# connector_schematic_1.net
KiCad netlist of a schematic drawn in EAGLE
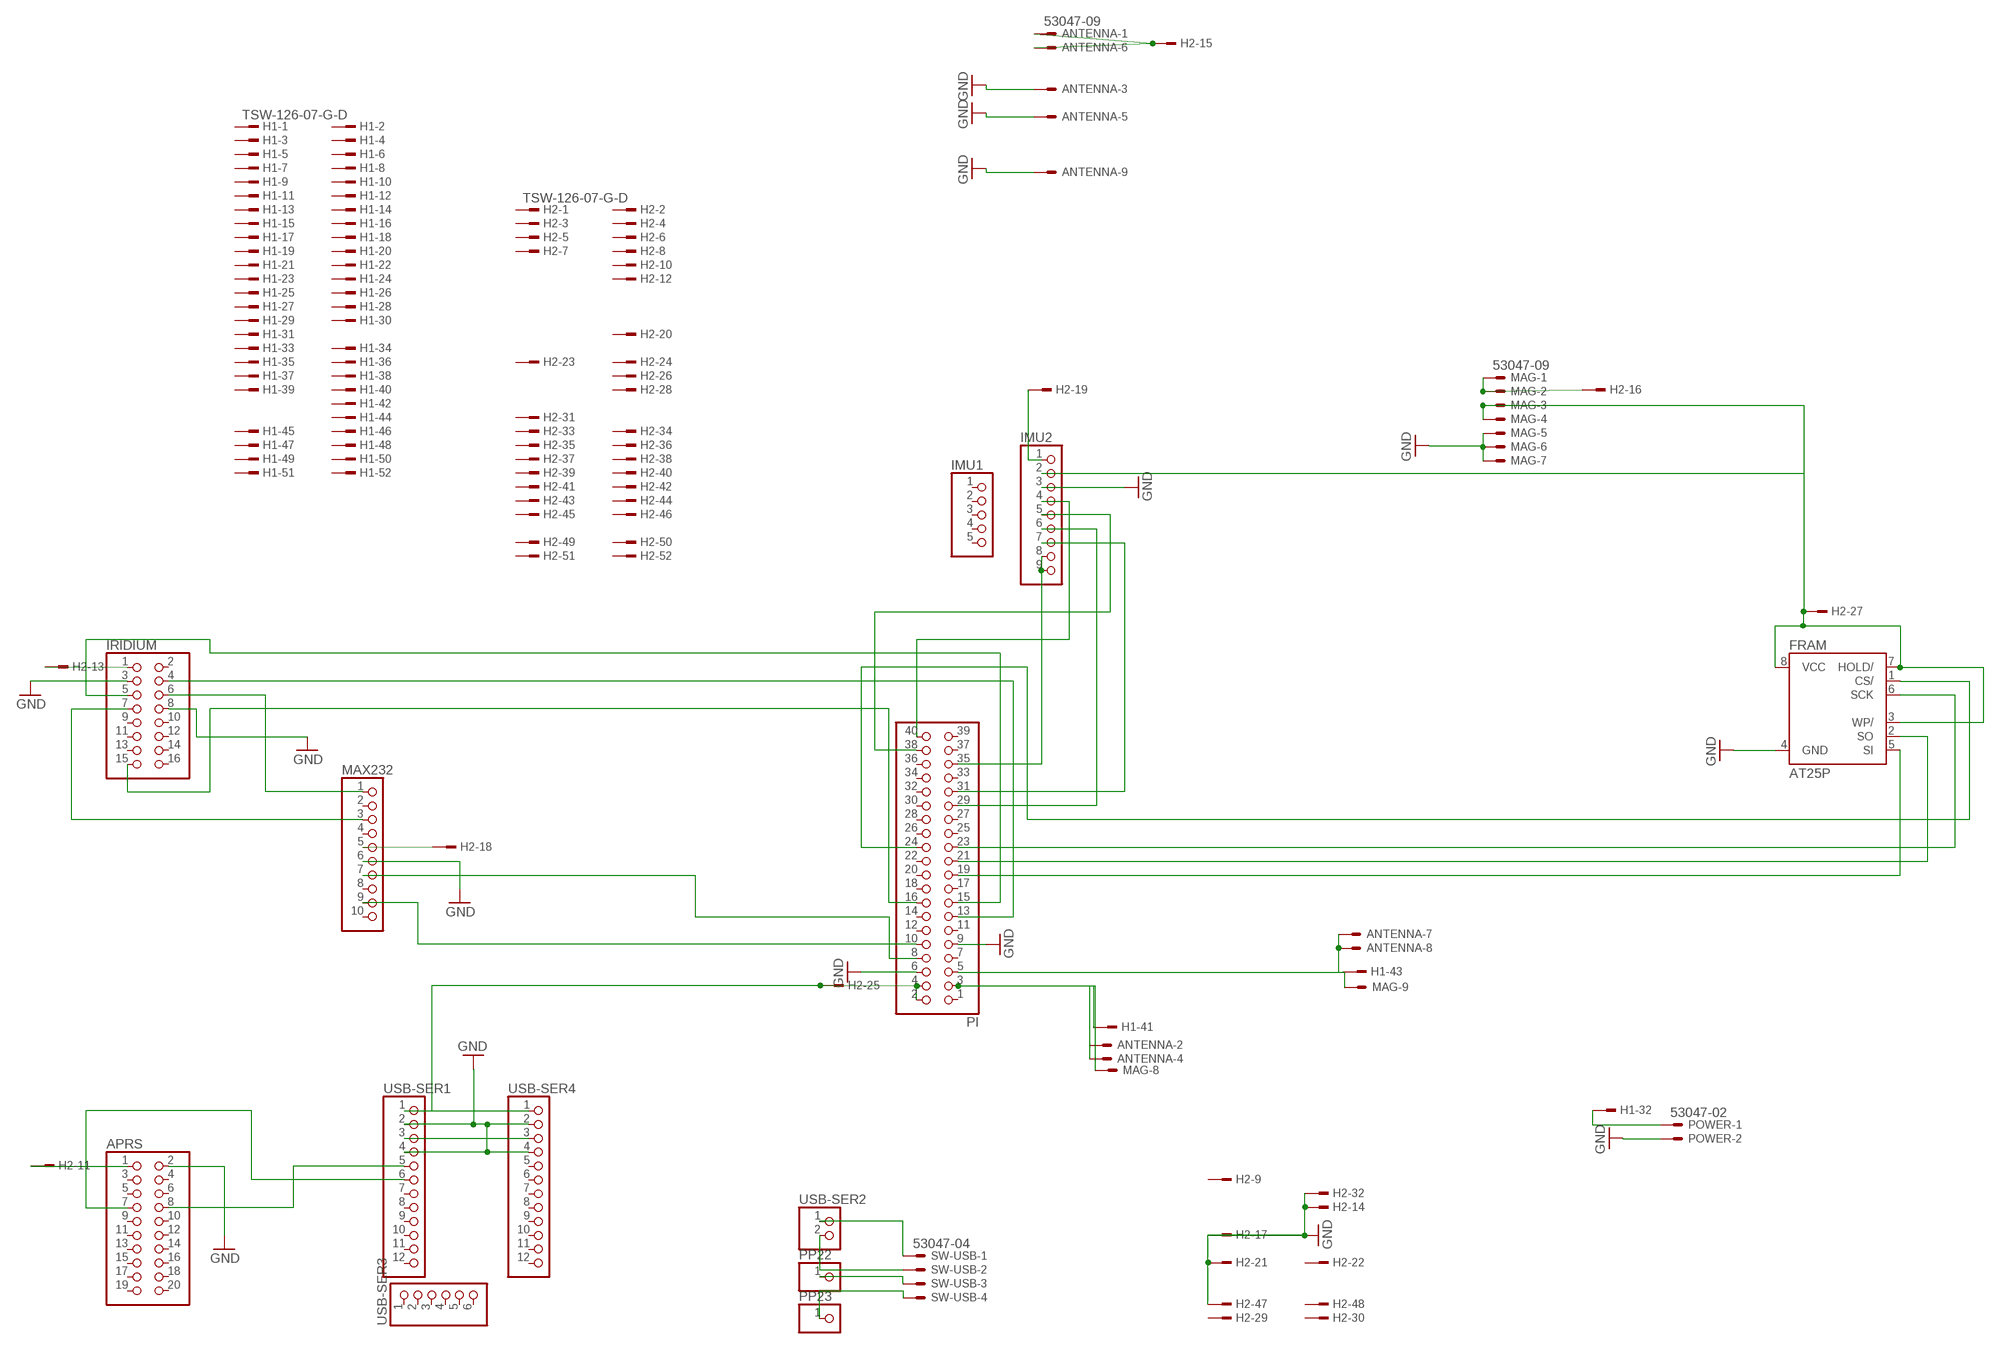
[diagram p0: schematic, sheet 1]

(export (version "E")
  (design (tool "Eeschema 10.0.6"))
  (components
    (comp (ref "ANTENNA")
      (value "53047-09")
      (footprint "eagle-import:53047-09")
      (fields (field (name "MF") "MOLEX") (field (name "MPN") "53047-0910"))
      (libsource (lib "eagle-import") (part "53?-09047"))
    )
    (comp (ref "APRS")
      (value "PINHD-2X10")
      (footprint "eagle-import:2X10")
      (libsource (lib "eagle-import") (part "PINHD-2X10"))
    )
    (comp (ref "FRAM")
      (value "AT25P")
      (footprint "eagle-import:DIL08")
      (fields (field (name "MPN") "CAT25040LI-G"))
      (libsource (lib "eagle-import") (part "AT25P"))
    )
    (comp (ref "H1")
      (value "TSW-126-07-G-D")
      (footprint "eagle-import:TSW-126-XX-G-D")
      (fields (field (name "MF") "Samtec Inc."))
      (libsource (lib "eagle-import") (part "TSW-126--G-D07"))
    )
    (comp (ref "H2")
      (value "TSW-126-07-G-D")
      (footprint "eagle-import:TSW-126-XX-G-D")
      (fields (field (name "MF") "Samtec Inc."))
      (libsource (lib "eagle-import") (part "TSW-126--G-D07"))
    )
    (comp (ref "IMU1")
      (value "PINHD-1X5")
      (footprint "eagle-import:1X05")
      (libsource (lib "eagle-import") (part "PINHD-1X5"))
    )
    (comp (ref "IMU2")
      (value "PINHD-1X9")
      (footprint "eagle-import:1X09")
      (libsource (lib "eagle-import") (part "PINHD-1X9"))
    )
    (comp (ref "IRIDIUM")
      (value "PINHD-2X8")
      (footprint "eagle-import:2X08")
      (libsource (lib "eagle-import") (part "PINHD-2X8"))
    )
    (comp (ref "MAG")
      (value "53047-09")
      (footprint "eagle-import:53047-09")
      (fields (field (name "MF") "MOLEX") (field (name "MPN") "53047-0910"))
      (libsource (lib "eagle-import") (part "53?-09047"))
    )
    (comp (ref "MAX232")
      (value "PINHD-1X10")
      (footprint "eagle-import:1X10")
      (libsource (lib "eagle-import") (part "PINHD-1X10"))
    )
    (comp (ref "PI")
      (value "PINHD-2X20")
      (footprint "eagle-import:2X20")
      (libsource (lib "eagle-import") (part "PINHD-2X20"))
    )
    (comp (ref "POWER")
      (value "53047-02")
      (footprint "eagle-import:53047-02")
      (fields (field (name "MF") "MOLEX") (field (name "MPN") "53047-0210"))
      (libsource (lib "eagle-import") (part "53?-02047"))
    )
    (comp (ref "PP22")
      (value "PINHD-1X1")
      (footprint "eagle-import:1X01")
      (libsource (lib "eagle-import") (part "PINHD-1X1"))
    )
    (comp (ref "PP23")
      (value "PINHD-1X1")
      (footprint "eagle-import:1X01")
      (libsource (lib "eagle-import") (part "PINHD-1X1"))
    )
    (comp (ref "SW-USB")
      (value "53047-04")
      (footprint "eagle-import:53047-04")
      (fields (field (name "MF") "WALDOM/MOLEX") (field (name "MPN") "53047-0410"))
      (libsource (lib "eagle-import") (part "53?-04047"))
    )
    (comp (ref "USB-SER1")
      (value "PINHD-1X12")
      (footprint "eagle-import:1X12")
      (libsource (lib "eagle-import") (part "PINHD-1X12"))
    )
    (comp (ref "USB-SER2")
      (value "PINHD-1X2")
      (footprint "eagle-import:1X02")
      (libsource (lib "eagle-import") (part "PINHD-1X2"))
    )
    (comp (ref "USB-SER3")
      (value "PINHD-1X6")
      (footprint "eagle-import:1X06")
      (libsource (lib "eagle-import") (part "PINHD-1X6"))
    )
    (comp (ref "USB-SER4")
      (value "PINHD-1X12")
      (footprint "eagle-import:1X12")
      (libsource (lib "eagle-import") (part "PINHD-1X12"))
    )
  )
  (nets
    (net (code "1") (name "GND") (class "Default")
      (node (ref "ANTENNA") (pin "3") (pinfunction "S_3") (pintype "passive"))
      (node (ref "ANTENNA") (pin "5") (pinfunction "S_5") (pintype "passive"))
      (node (ref "ANTENNA") (pin "9") (pinfunction "S_9") (pintype "passive"))
      (node (ref "APRS") (pin "2") (pinfunction "2_2") (pintype "passive"))
      (node (ref "FRAM") (pin "4") (pinfunction "GND_4") (pintype "power_in"))
      (node (ref "H2") (pin "14") (pinfunction "1_14") (pintype "passive"))
      (node (ref "H2") (pin "17") (pinfunction "1_17") (pintype "passive"))
      (node (ref "H2") (pin "21") (pinfunction "1_21") (pintype "passive"))
      (node (ref "H2") (pin "32") (pinfunction "1_32") (pintype "passive"))
      (node (ref "H2") (pin "47") (pinfunction "1_47") (pintype "passive"))
      (node (ref "IMU2") (pin "3") (pinfunction "3_3") (pintype "passive"))
      (node (ref "IRIDIUM") (pin "3") (pinfunction "3_3") (pintype "passive"))
      (node (ref "IRIDIUM") (pin "8") (pinfunction "8_8") (pintype "passive"))
      (node (ref "MAG") (pin "5") (pinfunction "S_5") (pintype "passive"))
      (node (ref "MAG") (pin "6") (pinfunction "S_6") (pintype "passive"))
      (node (ref "MAG") (pin "7") (pinfunction "S_7") (pintype "passive"))
      (node (ref "MAX232") (pin "6") (pinfunction "6_6") (pintype "passive"))
      (node (ref "PI") (pin "6") (pinfunction "6_6") (pintype "passive"))
      (node (ref "PI") (pin "9") (pinfunction "9_9") (pintype "passive"))
      (node (ref "POWER") (pin "2") (pinfunction "S_2") (pintype "passive"))
      (node (ref "USB-SER1") (pin "2") (pinfunction "2_2") (pintype "passive"))
      (node (ref "USB-SER1") (pin "4") (pinfunction "4_4") (pintype "passive"))
      (node (ref "USB-SER4") (pin "2") (pinfunction "2_2") (pintype "passive"))
      (node (ref "USB-SER4") (pin "4") (pinfunction "4_4") (pintype "passive"))
    )
    (net (code "2") (name "Net-(ANTENNAA-S)") (class "Default")
      (node (ref "ANTENNA") (pin "1") (pinfunction "S_1") (pintype "passive"))
      (node (ref "ANTENNA") (pin "6") (pinfunction "S_6") (pintype "passive"))
      (node (ref "H2") (pin "15") (pinfunction "1_15") (pintype "passive"))
    )
    (net (code "3") (name "Net-(ANTENNAB-S)") (class "Default")
      (node (ref "ANTENNA") (pin "2") (pinfunction "S_2") (pintype "passive"))
      (node (ref "ANTENNA") (pin "4") (pinfunction "S_4") (pintype "passive"))
      (node (ref "H1") (pin "41") (pinfunction "1_41") (pintype "passive"))
      (node (ref "MAG") (pin "8") (pinfunction "S_8") (pintype "passive"))
      (node (ref "PI") (pin "3") (pinfunction "3_3") (pintype "passive"))
    )
    (net (code "4") (name "Net-(ANTENNAG-S)") (class "Default")
      (node (ref "ANTENNA") (pin "7") (pinfunction "S_7") (pintype "passive"))
      (node (ref "ANTENNA") (pin "8") (pinfunction "S_8") (pintype "passive"))
      (node (ref "H1") (pin "43") (pinfunction "1_43") (pintype "passive"))
      (node (ref "MAG") (pin "9") (pinfunction "S_9") (pintype "passive"))
      (node (ref "PI") (pin "5") (pinfunction "5_5") (pintype "passive"))
    )
    (net (code "5") (name "Net-(APRS-Pad7)") (class "Default")
      (node (ref "APRS") (pin "7") (pinfunction "7_7") (pintype "passive"))
      (node (ref "USB-SER1") (pin "6") (pinfunction "6_6") (pintype "passive"))
    )
    (net (code "6") (name "Net-(APRS-Pad8)") (class "Default")
      (node (ref "APRS") (pin "8") (pinfunction "8_8") (pintype "passive"))
      (node (ref "USB-SER1") (pin "5") (pinfunction "5_5") (pintype "passive"))
    )
    (net (code "7") (name "Net-(FRAM-CS{slash})") (class "Default")
      (node (ref "FRAM") (pin "1") (pinfunction "CS/_1") (pintype "input"))
      (node (ref "PI") (pin "24") (pinfunction "24_24") (pintype "passive"))
    )
    (net (code "8") (name "Net-(FRAM-HOLD{slash})") (class "Default")
      (node (ref "FRAM") (pin "3") (pinfunction "WP/_3") (pintype "input"))
      (node (ref "FRAM") (pin "7") (pinfunction "HOLD/_7") (pintype "input"))
      (node (ref "FRAM") (pin "8") (pinfunction "VCC_8") (pintype "power_in"))
      (node (ref "H2") (pin "27") (pinfunction "1_27") (pintype "passive"))
      (node (ref "IMU2") (pin "2") (pinfunction "2_2") (pintype "passive"))
      (node (ref "MAG") (pin "3") (pinfunction "S_3") (pintype "passive"))
      (node (ref "MAG") (pin "4") (pinfunction "S_4") (pintype "passive"))
    )
    (net (code "9") (name "Net-(FRAM-SCK)") (class "Default")
      (node (ref "FRAM") (pin "6") (pinfunction "SCK_6") (pintype "bidirectional"))
      (node (ref "PI") (pin "23") (pinfunction "23_23") (pintype "passive"))
    )
    (net (code "10") (name "Net-(FRAM-SI)") (class "Default")
      (node (ref "FRAM") (pin "5") (pinfunction "SI_5") (pintype "bidirectional"))
      (node (ref "PI") (pin "19") (pinfunction "19_19") (pintype "passive"))
    )
    (net (code "11") (name "Net-(FRAM-SO)") (class "Default")
      (node (ref "FRAM") (pin "2") (pinfunction "SO_2") (pintype "input"))
      (node (ref "PI") (pin "21") (pinfunction "21_21") (pintype "passive"))
    )
    (net (code "12") (name "Net-(H1Z-1)") (class "Default")
      (node (ref "H1") (pin "32") (pinfunction "1_32") (pintype "passive"))
      (node (ref "POWER") (pin "1") (pinfunction "S_1") (pintype "passive"))
    )
    (net (code "13") (name "Net-(H2C-1)") (class "Default")
      (node (ref "APRS") (pin "1") (pinfunction "1_1") (pintype "passive"))
      (node (ref "H2") (pin "11") (pinfunction "1_11") (pintype "passive"))
    )
    (net (code "14") (name "Net-(H2E-1)") (class "Default")
      (node (ref "H2") (pin "13") (pinfunction "1_13") (pintype "passive"))
      (node (ref "IRIDIUM") (pin "1") (pinfunction "1_1") (pintype "passive"))
    )
    (net (code "15") (name "Net-(H2H-1)") (class "Default")
      (node (ref "H2") (pin "16") (pinfunction "1_16") (pintype "passive"))
      (node (ref "MAG") (pin "1") (pinfunction "S_1") (pintype "passive"))
      (node (ref "MAG") (pin "2") (pinfunction "S_2") (pintype "passive"))
    )
    (net (code "16") (name "Net-(H2J-1)") (class "Default")
      (node (ref "H2") (pin "18") (pinfunction "1_18") (pintype "passive"))
      (node (ref "MAX232") (pin "5") (pinfunction "5_5") (pintype "passive"))
    )
    (net (code "17") (name "Net-(H2K-1)") (class "Default")
      (node (ref "H2") (pin "19") (pinfunction "1_19") (pintype "passive"))
      (node (ref "IMU2") (pin "1") (pinfunction "1_1") (pintype "passive"))
    )
    (net (code "18") (name "Net-(H2R-1)") (class "Default")
      (node (ref "H2") (pin "25") (pinfunction "1_25") (pintype "passive"))
      (node (ref "PI") (pin "2") (pinfunction "2_2") (pintype "passive"))
      (node (ref "PI") (pin "4") (pinfunction "4_4") (pintype "passive"))
      (node (ref "USB-SER1") (pin "1") (pinfunction "1_1") (pintype "passive"))
      (node (ref "USB-SER4") (pin "1") (pinfunction "1_1") (pintype "passive"))
    )
    (net (code "19") (name "Net-(IMU2-Pad4)") (class "Default")
      (node (ref "IMU2") (pin "4") (pinfunction "4_4") (pintype "passive"))
      (node (ref "PI") (pin "40") (pinfunction "40_40") (pintype "passive"))
    )
    (net (code "20") (name "Net-(IMU2-Pad5)") (class "Default")
      (node (ref "IMU2") (pin "5") (pinfunction "5_5") (pintype "passive"))
      (node (ref "PI") (pin "38") (pinfunction "38_38") (pintype "passive"))
    )
    (net (code "21") (name "Net-(IMU2-Pad6)") (class "Default")
      (node (ref "IMU2") (pin "6") (pinfunction "6_6") (pintype "passive"))
      (node (ref "PI") (pin "29") (pinfunction "29_29") (pintype "passive"))
    )
    (net (code "22") (name "Net-(IMU2-Pad7)") (class "Default")
      (node (ref "IMU2") (pin "7") (pinfunction "7_7") (pintype "passive"))
      (node (ref "PI") (pin "31") (pinfunction "31_31") (pintype "passive"))
    )
    (net (code "23") (name "Net-(IMU2-Pad8)") (class "Default")
      (node (ref "IMU2") (pin "8") (pinfunction "8_8") (pintype "passive"))
      (node (ref "IMU2") (pin "9") (pinfunction "9_9") (pintype "passive"))
      (node (ref "PI") (pin "35") (pinfunction "35_35") (pintype "passive"))
    )
    (net (code "24") (name "Net-(IRIDIUM-Pad4)") (class "Default")
      (node (ref "IRIDIUM") (pin "4") (pinfunction "4_4") (pintype "passive"))
      (node (ref "PI") (pin "13") (pinfunction "13_13") (pintype "passive"))
    )
    (net (code "25") (name "Net-(IRIDIUM-Pad5)") (class "Default")
      (node (ref "IRIDIUM") (pin "5") (pinfunction "5_5") (pintype "passive"))
      (node (ref "PI") (pin "15") (pinfunction "15_15") (pintype "passive"))
    )
    (net (code "26") (name "Net-(IRIDIUM-Pad6)") (class "Default")
      (node (ref "IRIDIUM") (pin "6") (pinfunction "6_6") (pintype "passive"))
      (node (ref "MAX232") (pin "1") (pinfunction "1_1") (pintype "passive"))
    )
    (net (code "27") (name "Net-(IRIDIUM-Pad7)") (class "Default")
      (node (ref "IRIDIUM") (pin "7") (pinfunction "7_7") (pintype "passive"))
      (node (ref "MAX232") (pin "3") (pinfunction "3_3") (pintype "passive"))
    )
    (net (code "28") (name "Net-(IRIDIUM-Pad15)") (class "Default")
      (node (ref "IRIDIUM") (pin "15") (pinfunction "15_15") (pintype "passive"))
      (node (ref "PI") (pin "16") (pinfunction "16_16") (pintype "passive"))
    )
    (net (code "29") (name "Net-(MAX232-Pad7)") (class "Default")
      (node (ref "MAX232") (pin "7") (pinfunction "7_7") (pintype "passive"))
      (node (ref "PI") (pin "8") (pinfunction "8_8") (pintype "passive"))
    )
    (net (code "30") (name "Net-(MAX232-Pad9)") (class "Default")
      (node (ref "MAX232") (pin "9") (pinfunction "9_9") (pintype "passive"))
      (node (ref "PI") (pin "10") (pinfunction "10_10") (pintype "passive"))
    )
    (net (code "31") (name "Net-(SW-USBB-S)") (class "Default")
      (node (ref "SW-USB") (pin "2") (pinfunction "S_2") (pintype "passive"))
      (node (ref "USB-SER2") (pin "2") (pinfunction "2_2") (pintype "passive"))
    )
    (net (code "32") (name "Net-(SW-USBC-S)") (class "Default")
      (node (ref "PP22") (pin "1") (pinfunction "1_1") (pintype "passive"))
      (node (ref "SW-USB") (pin "3") (pinfunction "S_3") (pintype "passive"))
    )
    (net (code "33") (name "Net-(SW-USBD-S)") (class "Default")
      (node (ref "PP23") (pin "1") (pinfunction "1_1") (pintype "passive"))
      (node (ref "SW-USB") (pin "4") (pinfunction "S_4") (pintype "passive"))
    )
    (net (code "34") (name "Net-(USB-SER1-Pad3)") (class "Default")
      (node (ref "USB-SER1") (pin "3") (pinfunction "3_3") (pintype "passive"))
      (node (ref "USB-SER4") (pin "3") (pinfunction "3_3") (pintype "passive"))
    )
    (net (code "35") (name "unconnected-(APRS-Pad3)") (class "Default")
      (node (ref "APRS") (pin "3") (pinfunction "3_3") (pintype "passive"))
    )
    (net (code "36") (name "unconnected-(APRS-Pad4)") (class "Default")
      (node (ref "APRS") (pin "4") (pinfunction "4_4") (pintype "passive"))
    )
    (net (code "37") (name "unconnected-(APRS-Pad5)") (class "Default")
      (node (ref "APRS") (pin "5") (pinfunction "5_5") (pintype "passive"))
    )
    (net (code "38") (name "unconnected-(APRS-Pad6)") (class "Default")
      (node (ref "APRS") (pin "6") (pinfunction "6_6") (pintype "passive"))
    )
    (net (code "39") (name "unconnected-(APRS-Pad9)") (class "Default")
      (node (ref "APRS") (pin "9") (pinfunction "9_9") (pintype "passive"))
    )
    (net (code "40") (name "unconnected-(APRS-Pad10)") (class "Default")
      (node (ref "APRS") (pin "10") (pinfunction "10_10") (pintype "passive"))
    )
    (net (code "41") (name "unconnected-(APRS-Pad11)") (class "Default")
      (node (ref "APRS") (pin "11") (pinfunction "11_11") (pintype "passive"))
    )
    (net (code "42") (name "unconnected-(APRS-Pad12)") (class "Default")
      (node (ref "APRS") (pin "12") (pinfunction "12_12") (pintype "passive"))
    )
    (net (code "43") (name "unconnected-(APRS-Pad13)") (class "Default")
      (node (ref "APRS") (pin "13") (pinfunction "13_13") (pintype "passive"))
    )
    (net (code "44") (name "unconnected-(APRS-Pad14)") (class "Default")
      (node (ref "APRS") (pin "14") (pinfunction "14_14") (pintype "passive"))
    )
    (net (code "45") (name "unconnected-(APRS-Pad15)") (class "Default")
      (node (ref "APRS") (pin "15") (pinfunction "15_15") (pintype "passive"))
    )
    (net (code "46") (name "unconnected-(APRS-Pad16)") (class "Default")
      (node (ref "APRS") (pin "16") (pinfunction "16_16") (pintype "passive"))
    )
    (net (code "47") (name "unconnected-(APRS-Pad17)") (class "Default")
      (node (ref "APRS") (pin "17") (pinfunction "17_17") (pintype "passive"))
    )
    (net (code "48") (name "unconnected-(APRS-Pad18)") (class "Default")
      (node (ref "APRS") (pin "18") (pinfunction "18_18") (pintype "passive"))
    )
    (net (code "49") (name "unconnected-(APRS-Pad19)") (class "Default")
      (node (ref "APRS") (pin "19") (pinfunction "19_19") (pintype "passive"))
    )
    (net (code "50") (name "unconnected-(APRS-Pad20)") (class "Default")
      (node (ref "APRS") (pin "20") (pinfunction "20_20") (pintype "passive"))
    )
    (net (code "51") (name "unconnected-(H1-Pad1)") (class "Default")
      (node (ref "H1") (pin "1") (pinfunction "1_1") (pintype "passive"))
    )
    (net (code "52") (name "unconnected-(H1AA-1-Pad33)") (class "Default")
      (node (ref "H1") (pin "33") (pinfunction "1_33") (pintype "passive"))
    )
    (net (code "53") (name "unconnected-(H1AB-1-Pad34)") (class "Default")
      (node (ref "H1") (pin "34") (pinfunction "1_34") (pintype "passive"))
    )
    (net (code "54") (name "unconnected-(H1AC-1-Pad35)") (class "Default")
      (node (ref "H1") (pin "35") (pinfunction "1_35") (pintype "passive"))
    )
    (net (code "55") (name "unconnected-(H1AD-1-Pad36)") (class "Default")
      (node (ref "H1") (pin "36") (pinfunction "1_36") (pintype "passive"))
    )
    (net (code "56") (name "unconnected-(H1AE-1-Pad37)") (class "Default")
      (node (ref "H1") (pin "37") (pinfunction "1_37") (pintype "passive"))
    )
    (net (code "57") (name "unconnected-(H1AF-1-Pad38)") (class "Default")
      (node (ref "H1") (pin "38") (pinfunction "1_38") (pintype "passive"))
    )
    (net (code "58") (name "unconnected-(H1AG-1-Pad39)") (class "Default")
      (node (ref "H1") (pin "39") (pinfunction "1_39") (pintype "passive"))
    )
    (net (code "59") (name "unconnected-(H1AH-1-Pad4)") (class "Default")
      (node (ref "H1") (pin "4") (pinfunction "1_4") (pintype "passive"))
    )
    (net (code "60") (name "unconnected-(H1AI-1-Pad40)") (class "Default")
      (node (ref "H1") (pin "40") (pinfunction "1_40") (pintype "passive"))
    )
    (net (code "61") (name "unconnected-(H1AK-1-Pad42)") (class "Default")
      (node (ref "H1") (pin "42") (pinfunction "1_42") (pintype "passive"))
    )
    (net (code "62") (name "unconnected-(H1AM-1-Pad44)") (class "Default")
      (node (ref "H1") (pin "44") (pinfunction "1_44") (pintype "passive"))
    )
    (net (code "63") (name "unconnected-(H1AN-1-Pad45)") (class "Default")
      (node (ref "H1") (pin "45") (pinfunction "1_45") (pintype "passive"))
    )
    (net (code "64") (name "unconnected-(H1AO-1-Pad46)") (class "Default")
      (node (ref "H1") (pin "46") (pinfunction "1_46") (pintype "passive"))
    )
    (net (code "65") (name "unconnected-(H1AP-1-Pad47)") (class "Default")
      (node (ref "H1") (pin "47") (pinfunction "1_47") (pintype "passive"))
    )
    (net (code "66") (name "unconnected-(H1AQ-1-Pad48)") (class "Default")
      (node (ref "H1") (pin "48") (pinfunction "1_48") (pintype "passive"))
    )
    (net (code "67") (name "unconnected-(H1AR-1-Pad49)") (class "Default")
      (node (ref "H1") (pin "49") (pinfunction "1_49") (pintype "passive"))
    )
    (net (code "68") (name "unconnected-(H1AS-1-Pad5)") (class "Default")
      (node (ref "H1") (pin "5") (pinfunction "1_5") (pintype "passive"))
    )
    (net (code "69") (name "unconnected-(H1AT-1-Pad50)") (class "Default")
      (node (ref "H1") (pin "50") (pinfunction "1_50") (pintype "passive"))
    )
    (net (code "70") (name "unconnected-(H1AU-1-Pad51)") (class "Default")
      (node (ref "H1") (pin "51") (pinfunction "1_51") (pintype "passive"))
    )
    (net (code "71") (name "unconnected-(H1AV-1-Pad52)") (class "Default")
      (node (ref "H1") (pin "52") (pinfunction "1_52") (pintype "passive"))
    )
    (net (code "72") (name "unconnected-(H1AW-1-Pad6)") (class "Default")
      (node (ref "H1") (pin "6") (pinfunction "1_6") (pintype "passive"))
    )
    (net (code "73") (name "unconnected-(H1AX-1-Pad7)") (class "Default")
      (node (ref "H1") (pin "7") (pinfunction "1_7") (pintype "passive"))
    )
    (net (code "74") (name "unconnected-(H1AY-1-Pad8)") (class "Default")
      (node (ref "H1") (pin "8") (pinfunction "1_8") (pintype "passive"))
    )
    (net (code "75") (name "unconnected-(H1AZ-1-Pad9)") (class "Default")
      (node (ref "H1") (pin "9") (pinfunction "1_9") (pintype "passive"))
    )
    (net (code "76") (name "unconnected-(H1B-1-Pad10)") (class "Default")
      (node (ref "H1") (pin "10") (pinfunction "1_10") (pintype "passive"))
    )
    (net (code "77") (name "unconnected-(H1C-1-Pad11)") (class "Default")
      (node (ref "H1") (pin "11") (pinfunction "1_11") (pintype "passive"))
    )
    (net (code "78") (name "unconnected-(H1D-1-Pad12)") (class "Default")
      (node (ref "H1") (pin "12") (pinfunction "1_12") (pintype "passive"))
    )
    (net (code "79") (name "unconnected-(H1E-1-Pad13)") (class "Default")
      (node (ref "H1") (pin "13") (pinfunction "1_13") (pintype "passive"))
    )
    (net (code "80") (name "unconnected-(H1F-1-Pad14)") (class "Default")
      (node (ref "H1") (pin "14") (pinfunction "1_14") (pintype "passive"))
    )
    (net (code "81") (name "unconnected-(H1G-1-Pad15)") (class "Default")
      (node (ref "H1") (pin "15") (pinfunction "1_15") (pintype "passive"))
    )
    (net (code "82") (name "unconnected-(H1H-1-Pad16)") (class "Default")
      (node (ref "H1") (pin "16") (pinfunction "1_16") (pintype "passive"))
    )
    (net (code "83") (name "unconnected-(H1I-1-Pad17)") (class "Default")
      (node (ref "H1") (pin "17") (pinfunction "1_17") (pintype "passive"))
    )
    (net (code "84") (name "unconnected-(H1J-1-Pad18)") (class "Default")
      (node (ref "H1") (pin "18") (pinfunction "1_18") (pintype "passive"))
    )
    (net (code "85") (name "unconnected-(H1K-1-Pad19)") (class "Default")
      (node (ref "H1") (pin "19") (pinfunction "1_19") (pintype "passive"))
    )
    (net (code "86") (name "unconnected-(H1L-1-Pad2)") (class "Default")
      (node (ref "H1") (pin "2") (pinfunction "1_2") (pintype "passive"))
    )
    (net (code "87") (name "unconnected-(H1M-1-Pad20)") (class "Default")
      (node (ref "H1") (pin "20") (pinfunction "1_20") (pintype "passive"))
    )
    (net (code "88") (name "unconnected-(H1N-1-Pad21)") (class "Default")
      (node (ref "H1") (pin "21") (pinfunction "1_21") (pintype "passive"))
    )
    (net (code "89") (name "unconnected-(H1O-1-Pad22)") (class "Default")
      (node (ref "H1") (pin "22") (pinfunction "1_22") (pintype "passive"))
    )
    (net (code "90") (name "unconnected-(H1P-1-Pad23)") (class "Default")
      (node (ref "H1") (pin "23") (pinfunction "1_23") (pintype "passive"))
    )
    (net (code "91") (name "unconnected-(H1Q-1-Pad24)") (class "Default")
      (node (ref "H1") (pin "24") (pinfunction "1_24") (pintype "passive"))
    )
    (net (code "92") (name "unconnected-(H1R-1-Pad25)") (class "Default")
      (node (ref "H1") (pin "25") (pinfunction "1_25") (pintype "passive"))
    )
    (net (code "93") (name "unconnected-(H1S-1-Pad26)") (class "Default")
      (node (ref "H1") (pin "26") (pinfunction "1_26") (pintype "passive"))
    )
    (net (code "94") (name "unconnected-(H1T-1-Pad27)") (class "Default")
      (node (ref "H1") (pin "27") (pinfunction "1_27") (pintype "passive"))
    )
    (net (code "95") (name "unconnected-(H1U-1-Pad28)") (class "Default")
      (node (ref "H1") (pin "28") (pinfunction "1_28") (pintype "passive"))
    )
    (net (code "96") (name "unconnected-(H1V-1-Pad29)") (class "Default")
      (node (ref "H1") (pin "29") (pinfunction "1_29") (pintype "passive"))
    )
    (net (code "97") (name "unconnected-(H1W-1-Pad3)") (class "Default")
      (node (ref "H1") (pin "3") (pinfunction "1_3") (pintype "passive"))
    )
    (net (code "98") (name "unconnected-(H1X-1-Pad30)") (class "Default")
      (node (ref "H1") (pin "30") (pinfunction "1_30") (pintype "passive"))
    )
    (net (code "99") (name "unconnected-(H1Y-1-Pad31)") (class "Default")
      (node (ref "H1") (pin "31") (pinfunction "1_31") (pintype "passive"))
    )
    (net (code "100") (name "unconnected-(H2-Pad1)") (class "Default")
      (node (ref "H2") (pin "1") (pinfunction "1_1") (pintype "passive"))
    )
    (net (code "101") (name "unconnected-(H2AA-1-Pad33)") (class "Default")
      (node (ref "H2") (pin "33") (pinfunction "1_33") (pintype "passive"))
    )
    (net (code "102") (name "unconnected-(H2AB-1-Pad34)") (class "Default")
      (node (ref "H2") (pin "34") (pinfunction "1_34") (pintype "passive"))
    )
    (net (code "103") (name "unconnected-(H2AC-1-Pad35)") (class "Default")
      (node (ref "H2") (pin "35") (pinfunction "1_35") (pintype "passive"))
    )
    (net (code "104") (name "unconnected-(H2AD-1-Pad36)") (class "Default")
      (node (ref "H2") (pin "36") (pinfunction "1_36") (pintype "passive"))
    )
    (net (code "105") (name "unconnected-(H2AE-1-Pad37)") (class "Default")
      (node (ref "H2") (pin "37") (pinfunction "1_37") (pintype "passive"))
    )
    (net (code "106") (name "unconnected-(H2AF-1-Pad38)") (class "Default")
      (node (ref "H2") (pin "38") (pinfunction "1_38") (pintype "passive"))
    )
    (net (code "107") (name "unconnected-(H2AG-1-Pad39)") (class "Default")
      (node (ref "H2") (pin "39") (pinfunction "1_39") (pintype "passive"))
    )
    (net (code "108") (name "unconnected-(H2AH-1-Pad4)") (class "Default")
      (node (ref "H2") (pin "4") (pinfunction "1_4") (pintype "passive"))
    )
    (net (code "109") (name "unconnected-(H2AI-1-Pad40)") (class "Default")
      (node (ref "H2") (pin "40") (pinfunction "1_40") (pintype "passive"))
    )
    (net (code "110") (name "unconnected-(H2AJ-1-Pad41)") (class "Default")
      (node (ref "H2") (pin "41") (pinfunction "1_41") (pintype "passive"))
    )
    (net (code "111") (name "unconnected-(H2AK-1-Pad42)") (class "Default")
      (node (ref "H2") (pin "42") (pinfunction "1_42") (pintype "passive"))
    )
    (net (code "112") (name "unconnected-(H2AL-1-Pad43)") (class "Default")
      (node (ref "H2") (pin "43") (pinfunction "1_43") (pintype "passive"))
    )
    (net (code "113") (name "unconnected-(H2AM-1-Pad44)") (class "Default")
      (node (ref "H2") (pin "44") (pinfunction "1_44") (pintype "passive"))
    )
    (net (code "114") (name "unconnected-(H2AN-1-Pad45)") (class "Default")
      (node (ref "H2") (pin "45") (pinfunction "1_45") (pintype "passive"))
    )
    (net (code "115") (name "unconnected-(H2AO-1-Pad46)") (class "Default")
      (node (ref "H2") (pin "46") (pinfunction "1_46") (pintype "passive"))
    )
    (net (code "116") (name "unconnected-(H2AQ-1-Pad48)") (class "Default")
      (node (ref "H2") (pin "48") (pinfunction "1_48") (pintype "passive"))
    )
    (net (code "117") (name "unconnected-(H2AR-1-Pad49)") (class "Default")
      (node (ref "H2") (pin "49") (pinfunction "1_49") (pintype "passive"))
    )
    (net (code "118") (name "unconnected-(H2AS-1-Pad5)") (class "Default")
      (node (ref "H2") (pin "5") (pinfunction "1_5") (pintype "passive"))
    )
    (net (code "119") (name "unconnected-(H2AT-1-Pad50)") (class "Default")
      (node (ref "H2") (pin "50") (pinfunction "1_50") (pintype "passive"))
    )
    (net (code "120") (name "unconnected-(H2AU-1-Pad51)") (class "Default")
      (node (ref "H2") (pin "51") (pinfunction "1_51") (pintype "passive"))
    )
    (net (code "121") (name "unconnected-(H2AV-1-Pad52)") (class "Default")
      (node (ref "H2") (pin "52") (pinfunction "1_52") (pintype "passive"))
    )
    (net (code "122") (name "unconnected-(H2AW-1-Pad6)") (class "Default")
      (node (ref "H2") (pin "6") (pinfunction "1_6") (pintype "passive"))
    )
    (net (code "123") (name "unconnected-(H2AX-1-Pad7)") (class "Default")
      (node (ref "H2") (pin "7") (pinfunction "1_7") (pintype "passive"))
    )
    (net (code "124") (name "unconnected-(H2AY-1-Pad8)") (class "Default")
      (node (ref "H2") (pin "8") (pinfunction "1_8") (pintype "passive"))
    )
    (net (code "125") (name "unconnected-(H2AZ-1-Pad9)") (class "Default")
      (node (ref "H2") (pin "9") (pinfunction "1_9") (pintype "passive"))
    )
    (net (code "126") (name "unconnected-(H2B-1-Pad10)") (class "Default")
      (node (ref "H2") (pin "10") (pinfunction "1_10") (pintype "passive"))
    )
    (net (code "127") (name "unconnected-(H2D-1-Pad12)") (class "Default")
      (node (ref "H2") (pin "12") (pinfunction "1_12") (pintype "passive"))
    )
    (net (code "128") (name "unconnected-(H2L-1-Pad2)") (class "Default")
      (node (ref "H2") (pin "2") (pinfunction "1_2") (pintype "passive"))
    )
    (net (code "129") (name "unconnected-(H2M-1-Pad20)") (class "Default")
      (node (ref "H2") (pin "20") (pinfunction "1_20") (pintype "passive"))
    )
    (net (code "130") (name "unconnected-(H2O-1-Pad22)") (class "Default")
      (node (ref "H2") (pin "22") (pinfunction "1_22") (pintype "passive"))
    )
    (net (code "131") (name "unconnected-(H2P-1-Pad23)") (class "Default")
      (node (ref "H2") (pin "23") (pinfunction "1_23") (pintype "passive"))
    )
    (net (code "132") (name "unconnected-(H2Q-1-Pad24)") (class "Default")
      (node (ref "H2") (pin "24") (pinfunction "1_24") (pintype "passive"))
    )
    (net (code "133") (name "unconnected-(H2S-1-Pad26)") (class "Default")
      (node (ref "H2") (pin "26") (pinfunction "1_26") (pintype "passive"))
    )
    (net (code "134") (name "unconnected-(H2U-1-Pad28)") (class "Default")
      (node (ref "H2") (pin "28") (pinfunction "1_28") (pintype "passive"))
    )
    (net (code "135") (name "unconnected-(H2V-1-Pad29)") (class "Default")
      (node (ref "H2") (pin "29") (pinfunction "1_29") (pintype "passive"))
    )
    (net (code "136") (name "unconnected-(H2W-1-Pad3)") (class "Default")
      (node (ref "H2") (pin "3") (pinfunction "1_3") (pintype "passive"))
    )
    (net (code "137") (name "unconnected-(H2X-1-Pad30)") (class "Default")
      (node (ref "H2") (pin "30") (pinfunction "1_30") (pintype "passive"))
    )
    (net (code "138") (name "unconnected-(H2Y-1-Pad31)") (class "Default")
      (node (ref "H2") (pin "31") (pinfunction "1_31") (pintype "passive"))
    )
    (net (code "139") (name "unconnected-(IMU1-Pad1)") (class "Default")
      (node (ref "IMU1") (pin "1") (pinfunction "1_1") (pintype "passive"))
    )
    (net (code "140") (name "unconnected-(IMU1-Pad2)") (class "Default")
      (node (ref "IMU1") (pin "2") (pinfunction "2_2") (pintype "passive"))
    )
    (net (code "141") (name "unconnected-(IMU1-Pad3)") (class "Default")
      (node (ref "IMU1") (pin "3") (pinfunction "3_3") (pintype "passive"))
    )
    (net (code "142") (name "unconnected-(IMU1-Pad4)") (class "Default")
      (node (ref "IMU1") (pin "4") (pinfunction "4_4") (pintype "passive"))
    )
    (net (code "143") (name "unconnected-(IMU1-Pad5)") (class "Default")
      (node (ref "IMU1") (pin "5") (pinfunction "5_5") (pintype "passive"))
    )
    (net (code "144") (name "unconnected-(IRIDIUM-Pad2)") (class "Default")
      (node (ref "IRIDIUM") (pin "2") (pinfunction "2_2") (pintype "passive"))
    )
    (net (code "145") (name "unconnected-(IRIDIUM-Pad9)") (class "Default")
      (node (ref "IRIDIUM") (pin "9") (pinfunction "9_9") (pintype "passive"))
    )
    (net (code "146") (name "unconnected-(IRIDIUM-Pad10)") (class "Default")
      (node (ref "IRIDIUM") (pin "10") (pinfunction "10_10") (pintype "passive"))
    )
    (net (code "147") (name "unconnected-(IRIDIUM-Pad11)") (class "Default")
      (node (ref "IRIDIUM") (pin "11") (pinfunction "11_11") (pintype "passive"))
    )
    (net (code "148") (name "unconnected-(IRIDIUM-Pad12)") (class "Default")
      (node (ref "IRIDIUM") (pin "12") (pinfunction "12_12") (pintype "passive"))
    )
    (net (code "149") (name "unconnected-(IRIDIUM-Pad13)") (class "Default")
      (node (ref "IRIDIUM") (pin "13") (pinfunction "13_13") (pintype "passive"))
    )
    (net (code "150") (name "unconnected-(IRIDIUM-Pad14)") (class "Default")
      (node (ref "IRIDIUM") (pin "14") (pinfunction "14_14") (pintype "passive"))
    )
    (net (code "151") (name "unconnected-(IRIDIUM-Pad16)") (class "Default")
      (node (ref "IRIDIUM") (pin "16") (pinfunction "16_16") (pintype "passive"))
    )
    (net (code "152") (name "unconnected-(MAX232-Pad2)") (class "Default")
      (node (ref "MAX232") (pin "2") (pinfunction "2_2") (pintype "passive"))
    )
    (net (code "153") (name "unconnected-(MAX232-Pad4)") (class "Default")
      (node (ref "MAX232") (pin "4") (pinfunction "4_4") (pintype "passive"))
    )
    (net (code "154") (name "unconnected-(MAX232-Pad8)") (class "Default")
      (node (ref "MAX232") (pin "8") (pinfunction "8_8") (pintype "passive"))
    )
    (net (code "155") (name "unconnected-(MAX232-Pad10)") (class "Default")
      (node (ref "MAX232") (pin "10") (pinfunction "10_10") (pintype "passive"))
    )
    (net (code "156") (name "unconnected-(PI-Pad1)") (class "Default")
      (node (ref "PI") (pin "1") (pinfunction "1_1") (pintype "passive"))
    )
    (net (code "157") (name "unconnected-(PI-Pad7)") (class "Default")
      (node (ref "PI") (pin "7") (pinfunction "7_7") (pintype "passive"))
    )
    (net (code "158") (name "unconnected-(PI-Pad11)") (class "Default")
      (node (ref "PI") (pin "11") (pinfunction "11_11") (pintype "passive"))
    )
    (net (code "159") (name "unconnected-(PI-Pad12)") (class "Default")
      (node (ref "PI") (pin "12") (pinfunction "12_12") (pintype "passive"))
    )
    (net (code "160") (name "unconnected-(PI-Pad14)") (class "Default")
      (node (ref "PI") (pin "14") (pinfunction "14_14") (pintype "passive"))
    )
    (net (code "161") (name "unconnected-(PI-Pad17)") (class "Default")
      (node (ref "PI") (pin "17") (pinfunction "17_17") (pintype "passive"))
    )
    (net (code "162") (name "unconnected-(PI-Pad18)") (class "Default")
      (node (ref "PI") (pin "18") (pinfunction "18_18") (pintype "passive"))
    )
    (net (code "163") (name "unconnected-(PI-Pad20)") (class "Default")
      (node (ref "PI") (pin "20") (pinfunction "20_20") (pintype "passive"))
    )
    (net (code "164") (name "unconnected-(PI-Pad22)") (class "Default")
      (node (ref "PI") (pin "22") (pinfunction "22_22") (pintype "passive"))
    )
    (net (code "165") (name "unconnected-(PI-Pad25)") (class "Default")
      (node (ref "PI") (pin "25") (pinfunction "25_25") (pintype "passive"))
    )
    (net (code "166") (name "unconnected-(PI-Pad26)") (class "Default")
      (node (ref "PI") (pin "26") (pinfunction "26_26") (pintype "passive"))
    )
    (net (code "167") (name "unconnected-(PI-Pad27)") (class "Default")
      (node (ref "PI") (pin "27") (pinfunction "27_27") (pintype "passive"))
    )
    (net (code "168") (name "unconnected-(PI-Pad28)") (class "Default")
      (node (ref "PI") (pin "28") (pinfunction "28_28") (pintype "passive"))
    )
    (net (code "169") (name "unconnected-(PI-Pad30)") (class "Default")
      (node (ref "PI") (pin "30") (pinfunction "30_30") (pintype "passive"))
    )
    (net (code "170") (name "unconnected-(PI-Pad32)") (class "Default")
      (node (ref "PI") (pin "32") (pinfunction "32_32") (pintype "passive"))
    )
    (net (code "171") (name "unconnected-(PI-Pad33)") (class "Default")
      (node (ref "PI") (pin "33") (pinfunction "33_33") (pintype "passive"))
    )
    (net (code "172") (name "unconnected-(PI-Pad34)") (class "Default")
      (node (ref "PI") (pin "34") (pinfunction "34_34") (pintype "passive"))
    )
    (net (code "173") (name "unconnected-(PI-Pad36)") (class "Default")
      (node (ref "PI") (pin "36") (pinfunction "36_36") (pintype "passive"))
    )
    (net (code "174") (name "unconnected-(PI-Pad37)") (class "Default")
      (node (ref "PI") (pin "37") (pinfunction "37_37") (pintype "passive"))
    )
    (net (code "175") (name "unconnected-(PI-Pad39)") (class "Default")
      (node (ref "PI") (pin "39") (pinfunction "39_39") (pintype "passive"))
    )
    (net (code "176") (name "unconnected-(SW-USBA-S-Pad1)") (class "Default")
      (node (ref "SW-USB") (pin "1") (pinfunction "S_1") (pintype "passive"))
    )
    (net (code "177") (name "unconnected-(USB-SER1-Pad7)") (class "Default")
      (node (ref "USB-SER1") (pin "7") (pinfunction "7_7") (pintype "passive"))
    )
    (net (code "178") (name "unconnected-(USB-SER1-Pad8)") (class "Default")
      (node (ref "USB-SER1") (pin "8") (pinfunction "8_8") (pintype "passive"))
    )
    (net (code "179") (name "unconnected-(USB-SER1-Pad9)") (class "Default")
      (node (ref "USB-SER1") (pin "9") (pinfunction "9_9") (pintype "passive"))
    )
    (net (code "180") (name "unconnected-(USB-SER1-Pad10)") (class "Default")
      (node (ref "USB-SER1") (pin "10") (pinfunction "10_10") (pintype "passive"))
    )
    (net (code "181") (name "unconnected-(USB-SER1-Pad11)") (class "Default")
      (node (ref "USB-SER1") (pin "11") (pinfunction "11_11") (pintype "passive"))
    )
    (net (code "182") (name "unconnected-(USB-SER1-Pad12)") (class "Default")
      (node (ref "USB-SER1") (pin "12") (pinfunction "12_12") (pintype "passive"))
    )
    (net (code "183") (name "unconnected-(USB-SER2-Pad1)") (class "Default")
      (node (ref "USB-SER2") (pin "1") (pinfunction "1_1") (pintype "passive"))
    )
    (net (code "184") (name "unconnected-(USB-SER3-Pad1)") (class "Default")
      (node (ref "USB-SER3") (pin "1") (pinfunction "1_1") (pintype "passive"))
    )
    (net (code "185") (name "unconnected-(USB-SER3-Pad2)") (class "Default")
      (node (ref "USB-SER3") (pin "2") (pinfunction "2_2") (pintype "passive"))
    )
    (net (code "186") (name "unconnected-(USB-SER3-Pad3)") (class "Default")
      (node (ref "USB-SER3") (pin "3") (pinfunction "3_3") (pintype "passive"))
    )
    (net (code "187") (name "unconnected-(USB-SER3-Pad4)") (class "Default")
      (node (ref "USB-SER3") (pin "4") (pinfunction "4_4") (pintype "passive"))
    )
    (net (code "188") (name "unconnected-(USB-SER3-Pad5)") (class "Default")
      (node (ref "USB-SER3") (pin "5") (pinfunction "5_5") (pintype "passive"))
    )
    (net (code "189") (name "unconnected-(USB-SER3-Pad6)") (class "Default")
      (node (ref "USB-SER3") (pin "6") (pinfunction "6_6") (pintype "passive"))
    )
    (net (code "190") (name "unconnected-(USB-SER4-Pad5)") (class "Default")
      (node (ref "USB-SER4") (pin "5") (pinfunction "5_5") (pintype "passive"))
    )
    (net (code "191") (name "unconnected-(USB-SER4-Pad6)") (class "Default")
      (node (ref "USB-SER4") (pin "6") (pinfunction "6_6") (pintype "passive"))
    )
    (net (code "192") (name "unconnected-(USB-SER4-Pad7)") (class "Default")
      (node (ref "USB-SER4") (pin "7") (pinfunction "7_7") (pintype "passive"))
    )
    (net (code "193") (name "unconnected-(USB-SER4-Pad8)") (class "Default")
      (node (ref "USB-SER4") (pin "8") (pinfunction "8_8") (pintype "passive"))
    )
    (net (code "194") (name "unconnected-(USB-SER4-Pad9)") (class "Default")
      (node (ref "USB-SER4") (pin "9") (pinfunction "9_9") (pintype "passive"))
    )
    (net (code "195") (name "unconnected-(USB-SER4-Pad10)") (class "Default")
      (node (ref "USB-SER4") (pin "10") (pinfunction "10_10") (pintype "passive"))
    )
    (net (code "196") (name "unconnected-(USB-SER4-Pad11)") (class "Default")
      (node (ref "USB-SER4") (pin "11") (pinfunction "11_11") (pintype "passive"))
    )
    (net (code "197") (name "unconnected-(USB-SER4-Pad12)") (class "Default")
      (node (ref "USB-SER4") (pin "12") (pinfunction "12_12") (pintype "passive"))
    )
  )
)
